# I_Sensing.net
KiCad netlist of a schematic drawn in Altium Designer
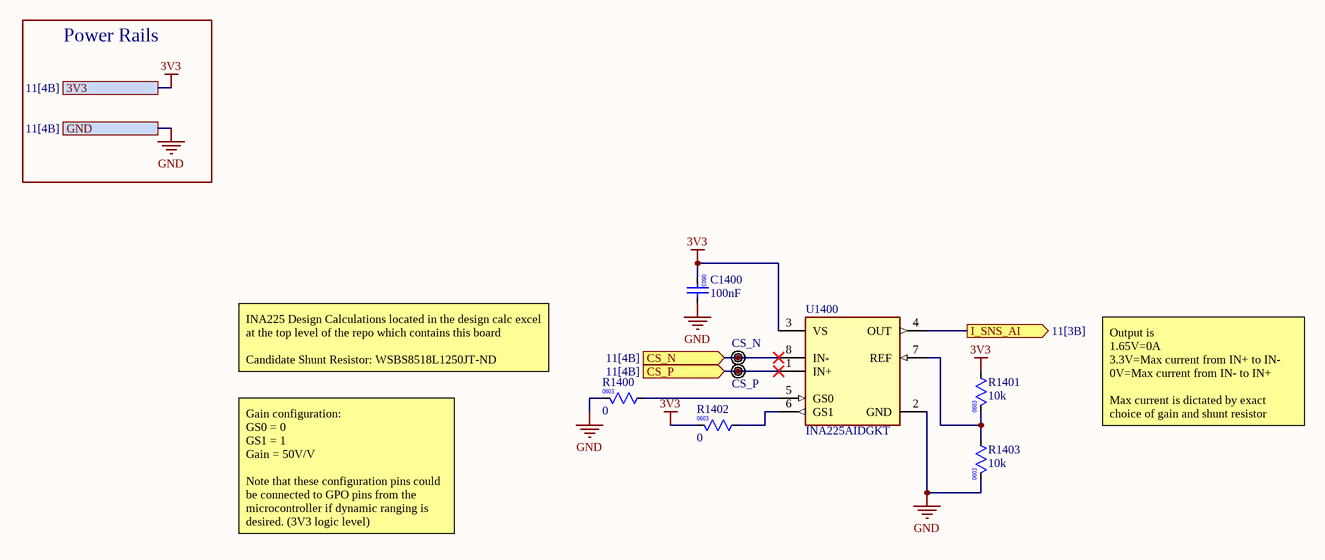
[diagram p0: I_Sensing.SchDoc]

(export (version "E")
  (design (tool "Eeschema 10.0.6"))
  (components
    (comp (ref "C1400")
      (value "100nF")
      (footprint "0603 Capacitor Footprint")
      (description "CAP CER 0.1UF 50V X7R 0603")
      (fields (field (name "TOLERANCE") "5%") (field (name "MANUFACTURER PART NUMBER") "CC0603JPX7R9BB104"))
      (libsource (lib "UBC Formula Electric") (part "0603 Generic Ceramic Capacitor"))
    )
    (comp (ref "R1400")
      (value "0")
      (footprint "RESC0603(1608)_L")
      (description "Jumper 0603")
      (libsource (lib "UBC Formula Electric") (part "RES-2"))
    )
    (comp (ref "R1401")
      (value "10k")
      (footprint "0603 Resistor Footprint")
      (description "RES SMD 10K OHM 1% 1/3W 0603")
      (fields (field (name "TOLERANCE") "1%") (field (name "POWER") "333mW"))
      (libsource (lib "UBC Formula Electric") (part "RES-2"))
    )
    (comp (ref "R1402")
      (value "0")
      (footprint "RESC0603(1608)_L")
      (description "Jumper 0603")
      (libsource (lib "UBC Formula Electric") (part "RES-2"))
    )
    (comp (ref "R1403")
      (value "10k")
      (footprint "0603 Resistor Footprint")
      (description "RES SMD 10K OHM 1% 1/3W 0603")
      (fields (field (name "TOLERANCE") "1%") (field (name "POWER") "333mW"))
      (libsource (lib "UBC Formula Electric") (part "RES-2"))
    )
    (comp (ref "TP1400")
      (value "CS_N")
      (footprint "TESTPOINT")
      (fields (field (name "SOURCE") "UBC Formula Electric.SchLib"))
      (libsource (lib "UBC Formula Electric") (part "Thru-Hole Test Point"))
    )
    (comp (ref "TP1401")
      (value "CS_P")
      (footprint "TESTPOINT")
      (fields (field (name "SOURCE") "UBC Formula Electric.SchLib"))
      (libsource (lib "UBC Formula Electric") (part "Thru-Hole Test Point"))
    )
    (comp (ref "U1400")
      (value "INA225AIDGKT")
      (footprint "FP-INA225AIDGKT-MFG")
      (description "IC MONITOR PWR/CUR BIDIR 8VSSOP")
      (fields
        (field (name "OCTOPART") "https://octopart.com/ina225aidgkt-texas+instruments-28946314")
        (field (name "MANUFACTURER") "Texas Instruments")
      )
      (libsource (lib "Altium Content Vault") (part "c359911d667b8e4eb68c8ff16fe5c28"))
    )
  )
  (nets
    (net (code "1") (name "/CS_N") (class "Default")
      (node (ref "TP1400") (pin "1") (pinfunction "TP_1") (pintype "passive"))
      (node (ref "U1400") (pin "8") (pinfunction "IN-_8") (pintype "tri_state"))
    )
    (net (code "2") (name "/CS_P") (class "Default")
      (node (ref "TP1401") (pin "1") (pinfunction "TP_1") (pintype "passive"))
      (node (ref "U1400") (pin "1") (pinfunction "IN+_1") (pintype "tri_state"))
    )
    (net (code "3") (name "/I_SNS_AI") (class "Default")
      (node (ref "U1400") (pin "4") (pinfunction "OUT_4") (pintype "output"))
    )
    (net (code "4") (name "3V3") (class "Default")
      (node (ref "C1400") (pin "2") (pinfunction "2_2") (pintype "passive"))
      (node (ref "R1401") (pin "1") (pinfunction "1_1") (pintype "passive"))
      (node (ref "R1402") (pin "2") (pinfunction "2_2") (pintype "passive"))
      (node (ref "U1400") (pin "3") (pinfunction "VS_3") (pintype "power_in"))
    )
    (net (code "5") (name "GND") (class "Default")
      (node (ref "C1400") (pin "1") (pinfunction "1_1") (pintype "passive"))
      (node (ref "R1400") (pin "2") (pinfunction "2_2") (pintype "passive"))
      (node (ref "R1403") (pin "2") (pinfunction "2_2") (pintype "passive"))
      (node (ref "U1400") (pin "2") (pinfunction "GND_2") (pintype "power_in"))
    )
    (net (code "6") (name "Net-(U1400-GS0)") (class "Default")
      (node (ref "R1400") (pin "1") (pinfunction "1_1") (pintype "passive"))
      (node (ref "U1400") (pin "5") (pinfunction "GS0_5") (pintype "input"))
    )
    (net (code "7") (name "Net-(U1400-GS1)") (class "Default")
      (node (ref "R1402") (pin "1") (pinfunction "1_1") (pintype "passive"))
      (node (ref "U1400") (pin "6") (pinfunction "GS1_6") (pintype "output"))
    )
    (net (code "8") (name "Net-(U1400-REF)") (class "Default")
      (node (ref "R1401") (pin "2") (pinfunction "2_2") (pintype "passive"))
      (node (ref "R1403") (pin "1") (pinfunction "1_1") (pintype "passive"))
      (node (ref "U1400") (pin "7") (pinfunction "REF_7") (pintype "input"))
    )
  )
)
